# SCH_FILTER_SOL_01_2025-06-17.net
KiCad netlist of a schematic drawn in EasyEDA
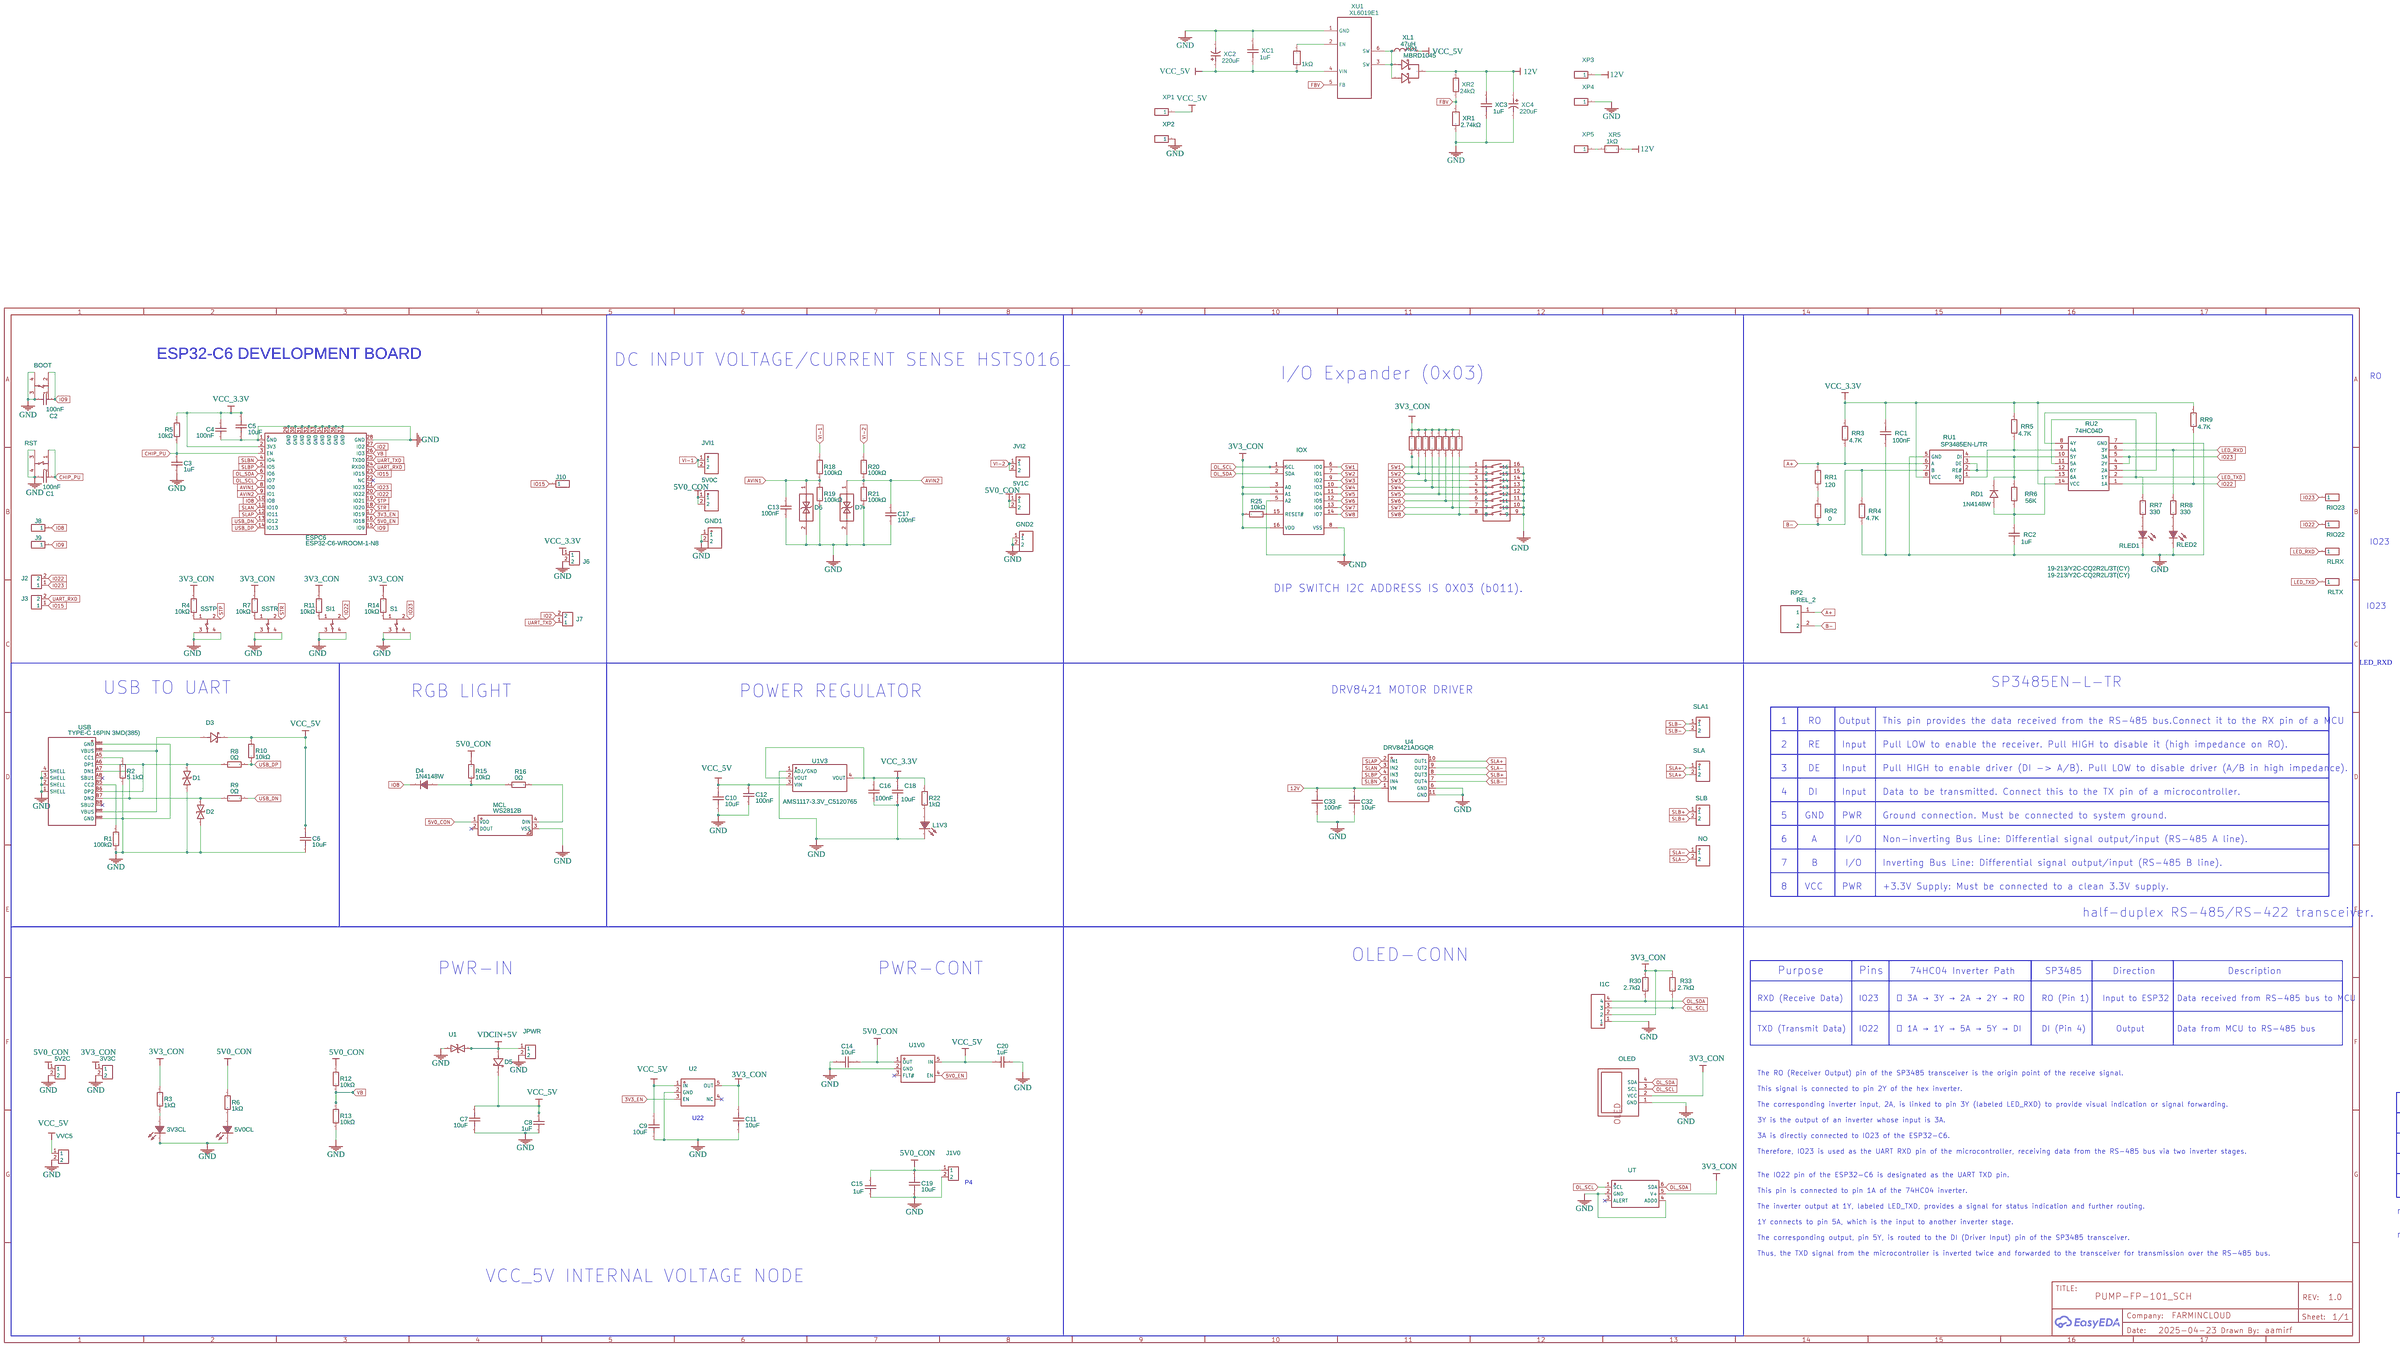
[diagram p0: schematic sheet]

(export (version "E")
  (design (tool "Eeschema 10.0.6"))
  (components
    (comp (ref "3V3C") (value "HD_1X2_2.54") (libsource (lib "") (part "HD_1X2_2.54_2")))
    (comp (ref "3V3CL")
      (value "KT-0603R")
      (fields (field (name "Manufacturer") "KENTO"))
      (libsource (lib "") (part "KT-0603R"))
    )
    (comp (ref "5V0C")
      (value "2060-451/998-404")
      (fields (field (name "Manufacturer") "WAGO(万可)"))
      (libsource (lib "") (part "2060-451/998-404_6"))
    )
    (comp (ref "5V0CL")
      (value "KT-0603R")
      (fields (field (name "Manufacturer") "KENTO"))
      (libsource (lib "") (part "KT-0603R_1"))
    )
    (comp (ref "5V1C")
      (value "2060-471/998-404")
      (fields (field (name "Manufacturer Part") "2060-451/998-404") (field (name "Manufacturer") "WAGO(万可)"))
      (libsource (lib "") (part "2060-451/998-404_4"))
    )
    (comp (ref "5V2C") (value "HD_1X2_2.54") (libsource (lib "") (part "HD_1X2_2.54_3")))
    (comp (ref "BOOT")
      (value "TS-1102SD-A-Q-R")
      (fields (field (name "Manufacturer") "XKB Connectivity(中国星坤)"))
      (libsource (lib "") (part "TS-1102SD-A-Q-R_3"))
    )
    (comp (ref "C1")
      (value "100nF")
      (fields
        (field (name "Manufacturer Part") "CL21B104KCFNNNE")
        (field (name "Manufacturer") "SAMSUNG(三星)")
      )
      (libsource (lib "") (part "CL21B104KCFNNNE_3"))
    )
    (comp (ref "C2")
      (value "100nF")
      (fields
        (field (name "Manufacturer Part") "CL21B104KCFNNNE")
        (field (name "Manufacturer") "SAMSUNG(三星)")
      )
      (libsource (lib "") (part "CL21B104KCFNNNE_2"))
    )
    (comp (ref "C3")
      (value "1uF")
      (fields
        (field (name "Manufacturer Part") "CL21B105KBFNNNE")
        (field (name "Manufacturer") "SAMSUNG(三星)")
      )
      (libsource (lib "") (part "CL21B105KBFNNNE_2"))
    )
    (comp (ref "C4")
      (value "100nF")
      (fields
        (field (name "Manufacturer Part") "CL21B104KCFNNNE")
        (field (name "Manufacturer") "SAMSUNG(三星)")
      )
      (libsource (lib "") (part "CL21B104KCFNNNE"))
    )
    (comp (ref "C5")
      (value "10uF")
      (fields
        (field (name "Manufacturer Part") "CL21A106KAYNNNE")
        (field (name "Manufacturer") "SAMSUNG(三星)")
      )
      (libsource (lib "") (part "CL21A106KAYNNNE"))
    )
    (comp (ref "C6")
      (value "10uF")
      (fields
        (field (name "Manufacturer Part") "CL21A106KAYNNNE")
        (field (name "Manufacturer") "SAMSUNG(三星)")
      )
      (libsource (lib "") (part "CL21A106KAYNNNE"))
    )
    (comp (ref "C7")
      (value "10uF")
      (fields
        (field (name "Manufacturer Part") "CL21A106KAYNNNE")
        (field (name "Manufacturer") "SAMSUNG(三星)")
      )
      (libsource (lib "") (part "CL21A106KAYNNNE_2"))
    )
    (comp (ref "C8")
      (value "1uF")
      (fields
        (field (name "Manufacturer Part") "CL21B105KBFNNNE")
        (field (name "Manufacturer") "SAMSUNG(三星)")
      )
      (libsource (lib "") (part "CL21B105KBFNNNE"))
    )
    (comp (ref "C9")
      (value "10uF")
      (fields
        (field (name "Manufacturer Part") "CL21A106KAYNNNE")
        (field (name "Manufacturer") "SAMSUNG(三星)")
      )
      (libsource (lib "") (part "CL21A106KAYNNNE_2"))
    )
    (comp (ref "C10")
      (value "10uF")
      (fields
        (field (name "Manufacturer Part") "CL21A106KAYNNNE")
        (field (name "Manufacturer") "SAMSUNG(三星)")
      )
      (libsource (lib "") (part "CL21A106KAYNNNE"))
    )
    (comp (ref "C11")
      (value "10uF")
      (fields
        (field (name "Manufacturer Part") "CL21A106KAYNNNE")
        (field (name "Manufacturer") "SAMSUNG(三星)")
      )
      (libsource (lib "") (part "CL21A106KAYNNNE"))
    )
    (comp (ref "C12")
      (value "100nF")
      (fields
        (field (name "Manufacturer Part") "CL21B104KCFNNNE")
        (field (name "Manufacturer") "SAMSUNG(三星)")
      )
      (libsource (lib "") (part "CL21B104KCFNNNE_1"))
    )
    (comp (ref "C13")
      (value "100nF")
      (fields
        (field (name "Manufacturer Part") "CL21B104KCFNNNE")
        (field (name "Manufacturer") "SAMSUNG(三星)")
      )
      (libsource (lib "") (part "CL21B104KCFNNNE"))
    )
    (comp (ref "C14")
      (value "10uF")
      (fields
        (field (name "Manufacturer Part") "CL21A106KAYNNNE")
        (field (name "Manufacturer") "SAMSUNG(三星)")
      )
      (libsource (lib "") (part "CL21A106KAYNNNE_1"))
    )
    (comp (ref "C15")
      (value "1uF")
      (fields
        (field (name "Manufacturer Part") "CL21B105KBFNNNE")
        (field (name "Manufacturer") "SAMSUNG(三星)")
      )
      (libsource (lib "") (part "CL21B105KBFNNNE"))
    )
    (comp (ref "C16")
      (value "100nF")
      (fields
        (field (name "Manufacturer Part") "CL21B104KCFNNNE")
        (field (name "Manufacturer") "SAMSUNG(三星)")
      )
      (libsource (lib "") (part "CL21B104KCFNNNE"))
    )
    (comp (ref "C17")
      (value "100nF")
      (fields
        (field (name "Manufacturer Part") "CL21B104KCFNNNE")
        (field (name "Manufacturer") "SAMSUNG(三星)")
      )
      (libsource (lib "") (part "CL21B104KCFNNNE_1"))
    )
    (comp (ref "C18")
      (value "10uF")
      (fields
        (field (name "Manufacturer Part") "CL21A106KAYNNNE")
        (field (name "Manufacturer") "SAMSUNG(三星)")
      )
      (libsource (lib "") (part "CL21A106KAYNNNE"))
    )
    (comp (ref "C19")
      (value "10uF")
      (fields
        (field (name "Manufacturer Part") "CL21A106KAYNNNE")
        (field (name "Manufacturer") "SAMSUNG(三星)")
      )
      (libsource (lib "") (part "CL21A106KAYNNNE"))
    )
    (comp (ref "C20")
      (value "1uF")
      (fields
        (field (name "Manufacturer Part") "CL21B105KBFNNNE")
        (field (name "Manufacturer") "SAMSUNG(三星)")
      )
      (libsource (lib "") (part "CL21B105KBFNNNE_1"))
    )
    (comp (ref "C32")
      (value "10uF")
      (fields (field (name "Manufacturer Part") "CGA4J1X7R0J106M125AD") (field (name "Manufacturer") "TDK"))
      (libsource (lib "") (part "CGA4J1X7R0J106M125AD"))
    )
    (comp (ref "C33")
      (value "100nF")
      (fields (field (name "Manufacturer Part") "CGA4J3X7T2E104K125AA") (field (name "Manufacturer") "TDK"))
      (libsource (lib "") (part "CGA4J3X7T2E104K125AA_C5331016"))
    )
    (comp (ref "D1")
      (value "LESD5D5.0CT1G")
      (fields (field (name "Manufacturer") "LRC(乐山无线电)"))
      (libsource (lib "") (part "LESD5D5.0CT1G"))
    )
    (comp (ref "D2")
      (value "LESD5D5.0CT1G")
      (fields (field (name "Manufacturer") "LRC(乐山无线电)"))
      (libsource (lib "") (part "LESD5D5.0CT1G"))
    )
    (comp (ref "D3")
      (value "K1N5819HW-7-F")
      (fields (field (name "Manufacturer") "KUU"))
      (libsource (lib "") (part "K1N5819HW-7-F"))
    )
    (comp (ref "D4")
      (value "1N4148W")
      (fields (field (name "Manufacturer") "HT(金誉)"))
      (libsource (lib "") (part "1N4148W"))
    )
    (comp (ref "D5")
      (value "K1N5819HW-7-F")
      (fields (field (name "Manufacturer") "KUU"))
      (libsource (lib "") (part "K1N5819HW-7-F_1"))
    )
    (comp (ref "D6")
      (value "KESD5311X")
      (fields (field (name "Manufacturer") "KUU"))
      (libsource (lib "") (part "KESD5311X"))
    )
    (comp (ref "D7")
      (value "KESD5311X")
      (fields (field (name "Manufacturer") "KUU"))
      (libsource (lib "") (part "KESD5311X"))
    )
    (comp (ref "ESPC6")
      (value "ESP32-C6-WROOM-1-N8")
      (fields (field (name "Manufacturer") "ESPRESSIF(乐鑫)"))
      (libsource (lib "") (part "ESP32-C6-WROOM-1-N8"))
    )
    (comp (ref "GND1")
      (value "2060-451/998-404")
      (fields (field (name "Manufacturer") "WAGO(万可)"))
      (libsource (lib "") (part "2060-451/998-404_2"))
    )
    (comp (ref "GND2")
      (value "2060-451/998-404")
      (fields (field (name "Manufacturer") "WAGO(万可)"))
      (libsource (lib "") (part "2060-451/998-404_2"))
    )
    (comp (ref "I1C")
      (value "X6511WV-04H-C30D60")
      (fields (field (name "Manufacturer") "XKB Connectivity(中国星坤)"))
      (libsource (lib "") (part "X6511WV-04H-C30D60"))
    )
    (comp (ref "IOS")
      (value "THS108J")
      (fields (field (name "Manufacturer") "ROCPU Switches(台普)"))
      (libsource (lib "") (part "THS108J"))
    )
    (comp (ref "IOX")
      (value "PCA9557PW,118")
      (fields (field (name "Manufacturer") "NXP(恩智浦)"))
      (libsource (lib "") (part "PCA9557PW,118"))
    )
    (comp (ref "J1V0") (value "HD_1X2_2.54") (libsource (lib "") (part "HD_1X2_2.54_6")))
    (comp (ref "J2") (value "HD_1X2_2.54") (libsource (lib "") (part "HD_1X2_2.54_5")))
    (comp (ref "J3") (value "HD_1X2_2.54") (libsource (lib "") (part "HD_1X2_2.54_5")))
    (comp (ref "J6") (value "HD_1X2_2.54") (libsource (lib "") (part "HD_1X2_2.54_4")))
    (comp (ref "J7") (value "HD_1X2_2.54") (libsource (lib "") (part "HD_1X2_2.54")))
    (comp (ref "J8") (value "HDR-M-2.54_1x1") (libsource (lib "") (part "HDR-M-2.54_1x1")))
    (comp (ref "J9") (value "HDR-M-2.54_1x1") (libsource (lib "") (part "HDR-M-2.54_1x1")))
    (comp (ref "J10") (value "HDR-M-2.54_1x1") (libsource (lib "") (part "HDR-M-2.54_1x1_1")))
    (comp (ref "JPWR") (value "HD_1X2_2.54") (libsource (lib "") (part "HD_1X2_2.54_1")))
    (comp (ref "JVI1")
      (value "2060-451/998-404")
      (fields (field (name "Manufacturer") "WAGO(万可)"))
      (libsource (lib "") (part "2060-451/998-404"))
    )
    (comp (ref "JVI2")
      (value "2060-451/998-404")
      (fields (field (name "Manufacturer") "WAGO(万可)"))
      (libsource (lib "") (part "2060-451/998-404"))
    )
    (comp (ref "L1V3")
      (value "KT-0603R")
      (fields (field (name "Manufacturer") "KENTO"))
      (libsource (lib "") (part "KT-0603R_2"))
    )
    (comp (ref "MCL")
      (value "WS2812B")
      (fields (field (name "Manufacturer Part") "WS2812B-V3") (field (name "Manufacturer") "worldsemi"))
      (libsource (lib "") (part "WS2812B"))
    )
    (comp (ref "NO")
      (value "2060-451/998-404")
      (fields (field (name "Manufacturer") "WAGO(万可)"))
      (libsource (lib "") (part "2060-451/998-404_5"))
    )
    (comp (ref "OLED")
      (value "GRINNAN_OLED 128X64 0,96\" I2C 4PIN")
      (fields (field (name "Manufacturer Part") "SSD1306 I2C OLED"))
      (libsource (lib "") (part "GRINNAN_OLED 128X64 0,96{dblquote} I2C 4PIN"))
    )
    (comp (ref "R1")
      (value "100kΩ")
      (fields
        (field (name "Manufacturer Part") "0805W8F1003T5E")
        (field (name "Manufacturer") "UNI-ROYAL(厚声)")
      )
      (libsource (lib "") (part "0805W8F1003T5E_C149504"))
    )
    (comp (ref "R2")
      (value "5.1kΩ")
      (fields
        (field (name "Manufacturer Part") "0805W8F5101T5E")
        (field (name "Manufacturer") "UNI-ROYAL(厚声)")
      )
      (libsource (lib "") (part "0805W8F5101T5E"))
    )
    (comp (ref "R3")
      (value "1kΩ")
      (fields
        (field (name "Manufacturer Part") "0805W8F1001T5E")
        (field (name "Manufacturer") "UNI-ROYAL(厚声)")
      )
      (libsource (lib "") (part "0805W8F1001T5E"))
    )
    (comp (ref "R4")
      (value "10kΩ")
      (fields
        (field (name "Manufacturer Part") "0805W8F1002T5E")
        (field (name "Manufacturer") "UNI-ROYAL(厚声)")
      )
      (libsource (lib "") (part "0805W8F1002T5E_1"))
    )
    (comp (ref "R5")
      (value "10kΩ")
      (fields
        (field (name "Manufacturer Part") "0805W8F1002T5E")
        (field (name "Manufacturer") "UNI-ROYAL(厚声)")
      )
      (libsource (lib "") (part "0805W8F1002T5E_1"))
    )
    (comp (ref "R6")
      (value "1kΩ")
      (fields
        (field (name "Manufacturer Part") "0805W8F1001T5E")
        (field (name "Manufacturer") "UNI-ROYAL(厚声)")
      )
      (libsource (lib "") (part "0805W8F1001T5E"))
    )
    (comp (ref "R7")
      (value "10kΩ")
      (fields
        (field (name "Manufacturer Part") "0805W8F1002T5E")
        (field (name "Manufacturer") "UNI-ROYAL(厚声)")
      )
      (libsource (lib "") (part "0805W8F1002T5E_1"))
    )
    (comp (ref "R8")
      (value "0Ω")
      (fields
        (field (name "Manufacturer Part") "0805W8F0000T5E")
        (field (name "Manufacturer") "UNI-ROYAL(厚声)")
      )
      (libsource (lib "") (part "0805W8F0000T5E"))
    )
    (comp (ref "R9")
      (value "0Ω")
      (fields
        (field (name "Manufacturer Part") "0805W8F0000T5E")
        (field (name "Manufacturer") "UNI-ROYAL(厚声)")
      )
      (libsource (lib "") (part "0805W8F0000T5E"))
    )
    (comp (ref "R10")
      (value "10kΩ")
      (fields
        (field (name "Manufacturer Part") "0805W8F1002T5E")
        (field (name "Manufacturer") "UNI-ROYAL(厚声)")
      )
      (libsource (lib "") (part "0805W8F1002T5E_1"))
    )
    (comp (ref "R11")
      (value "10kΩ")
      (fields
        (field (name "Manufacturer Part") "0805W8F1002T5E")
        (field (name "Manufacturer") "UNI-ROYAL(厚声)")
      )
      (libsource (lib "") (part "0805W8F1002T5E_1"))
    )
    (comp (ref "R12")
      (value "10kΩ")
      (fields
        (field (name "Manufacturer Part") "0805W8F1002T5E")
        (field (name "Manufacturer") "UNI-ROYAL(厚声)")
      )
      (libsource (lib "") (part "0805W8F1002T5E_1"))
    )
    (comp (ref "R13")
      (value "10kΩ")
      (fields
        (field (name "Manufacturer Part") "0805W8F1002T5E")
        (field (name "Manufacturer") "UNI-ROYAL(厚声)")
      )
      (libsource (lib "") (part "0805W8F1002T5E_1"))
    )
    (comp (ref "R14")
      (value "10kΩ")
      (fields
        (field (name "Manufacturer Part") "0805W8F1002T5E")
        (field (name "Manufacturer") "UNI-ROYAL(厚声)")
      )
      (libsource (lib "") (part "0805W8F1002T5E_1"))
    )
    (comp (ref "R15")
      (value "10kΩ")
      (fields
        (field (name "Manufacturer Part") "0805W8F1002T5E")
        (field (name "Manufacturer") "UNI-ROYAL(厚声)")
      )
      (libsource (lib "") (part "0805W8F1002T5E_1"))
    )
    (comp (ref "R16")
      (value "0Ω")
      (fields
        (field (name "Manufacturer Part") "0805W8F0000T5E")
        (field (name "Manufacturer") "UNI-ROYAL(厚声)")
      )
      (libsource (lib "") (part "0805W8F0000T5E"))
    )
    (comp (ref "R18")
      (value "100kΩ")
      (fields
        (field (name "Manufacturer Part") "0805W8F1003T5E")
        (field (name "Manufacturer") "UNI-ROYAL(厚声)")
      )
      (libsource (lib "") (part "0805W8F1003T5E_C149504"))
    )
    (comp (ref "R19")
      (value "100kΩ")
      (fields
        (field (name "Manufacturer Part") "0805W8F1003T5E")
        (field (name "Manufacturer") "UNI-ROYAL(厚声)")
      )
      (libsource (lib "") (part "0805W8F1003T5E_C149504"))
    )
    (comp (ref "R20")
      (value "100kΩ")
      (fields
        (field (name "Manufacturer Part") "0805W8F1003T5E")
        (field (name "Manufacturer") "UNI-ROYAL(厚声)")
      )
      (libsource (lib "") (part "0805W8F1003T5E_C149504"))
    )
    (comp (ref "R21")
      (value "100kΩ")
      (fields
        (field (name "Manufacturer Part") "0805W8F1003T5E")
        (field (name "Manufacturer") "UNI-ROYAL(厚声)")
      )
      (libsource (lib "") (part "0805W8F1003T5E_C149504"))
    )
    (comp (ref "R22")
      (value "1kΩ")
      (fields
        (field (name "Manufacturer Part") "0805W8F1001T5E")
        (field (name "Manufacturer") "UNI-ROYAL(厚声)")
      )
      (libsource (lib "") (part "0805W8F1001T5E"))
    )
    (comp (ref "R25")
      (value "10kΩ")
      (fields
        (field (name "Manufacturer Part") "0805W8F1002T5E")
        (field (name "Manufacturer") "UNI-ROYAL(厚声)")
      )
      (libsource (lib "") (part "0805W8F1002T5E"))
    )
    (comp (ref "R30")
      (value "2.7kΩ")
      (fields
        (field (name "Manufacturer Part") "0805W8F2701T5E")
        (field (name "Manufacturer") "UNI-ROYAL(厚声)")
      )
      (libsource (lib "") (part "0805W8F2701T5E"))
    )
    (comp (ref "R33")
      (value "2.7kΩ")
      (fields
        (field (name "Manufacturer Part") "0805W8F2701T5E")
        (field (name "Manufacturer") "UNI-ROYAL(厚声)")
      )
      (libsource (lib "") (part "0805W8F2701T5E"))
    )
    (comp (ref "RC1")
      (value "100nF")
      (fields (field (name "Manufacturer Part") "CC0603KRX7R9BB104") (field (name "Manufacturer") "YAGEO"))
      (libsource (lib "") (part "CC0603KRX7R9BB104"))
    )
    (comp (ref "RC2")
      (value "1uF")
      (fields (field (name "Manufacturer Part") "CL10A105KB8NNNC") (field (name "Manufacturer") "SAMSUNG"))
      (libsource (lib "") (part "CL10A105KB8NNNC"))
    )
    (comp (ref "RD1")
      (value "1N4148W")
      (fields (field (name "Manufacturer") "SEMTECH"))
      (libsource (lib "") (part "1N4148W_C81598"))
    )
    (comp (ref "RIO22")
      (value "Header-Male-2.54_1x1")
      (fields (field (name "Manufacturer Part") "2.54-1*1P针") (field (name "Manufacturer") "BOOMELE(博穆精密)"))
      (libsource (lib "") (part "Header-Male-2.54_1x1_1"))
    )
    (comp (ref "RIO23")
      (value "Header-Male-2.54_1x1")
      (fields (field (name "Manufacturer Part") "2.54-1*1P针") (field (name "Manufacturer") "BOOMELE(博穆精密)"))
      (libsource (lib "") (part "Header-Male-2.54_1x1_1"))
    )
    (comp (ref "RLED1")
      (value "19-213/Y2C-CQ2R2L/3T(CY)")
      (fields (field (name "Manufacturer") "EVERLIGHT"))
      (libsource (lib "") (part "19-213/Y2C-CQ2R2L/3T(CY)"))
    )
    (comp (ref "RLED2")
      (value "19-213/Y2C-CQ2R2L/3T(CY)")
      (fields (field (name "Manufacturer") "EVERLIGHT"))
      (libsource (lib "") (part "19-213/Y2C-CQ2R2L/3T(CY)"))
    )
    (comp (ref "RLRX")
      (value "Header-Male-2.54_1x1")
      (fields (field (name "Manufacturer Part") "2.54-1*1P针") (field (name "Manufacturer") "BOOMELE(博穆精密)"))
      (libsource (lib "") (part "Header-Male-2.54_1x1_2"))
    )
    (comp (ref "RLTX")
      (value "Header-Male-2.54_1x1")
      (fields (field (name "Manufacturer Part") "2.54-1*1P针") (field (name "Manufacturer") "BOOMELE(博穆精密)"))
      (libsource (lib "") (part "Header-Male-2.54_1x1_3"))
    )
    (comp (ref "RP2")
      (value "REL_2")
      (fields
        (field (name "Manufacturer Part") "WJ300V-5.0-2P")
        (field (name "Manufacturer") "KANGNEX(康奈克斯电气)")
      )
      (libsource (lib "") (part "WJ300V-5.0-2P"))
    )
    (comp (ref "RR1")
      (value "120")
      (fields (field (name "Manufacturer Part") "0603WAF1200T5E") (field (name "Manufacturer") "UniOhm"))
      (libsource (lib "") (part "0603WAF1200T5E"))
    )
    (comp (ref "RR2")
      (value "0")
      (fields (field (name "Manufacturer Part") "0603WAF0000T5E") (field (name "Manufacturer") "UniOhm"))
      (libsource (lib "") (part "0603WAF0000T5E"))
    )
    (comp (ref "RR3")
      (value "4.7K")
      (fields (field (name "Manufacturer Part") "0603WAF4701T5E") (field (name "Manufacturer") "UniOhm"))
      (libsource (lib "") (part "0603WAF4701T5E"))
    )
    (comp (ref "RR4")
      (value "4.7K")
      (fields (field (name "Manufacturer Part") "0603WAF4701T5E") (field (name "Manufacturer") "UniOhm"))
      (libsource (lib "") (part "0603WAF4701T5E"))
    )
    (comp (ref "RR5")
      (value "4.7K")
      (fields (field (name "Manufacturer Part") "0603WAF4701T5E") (field (name "Manufacturer") "UniOhm"))
      (libsource (lib "") (part "0603WAF4701T5E"))
    )
    (comp (ref "RR6")
      (value "56K")
      (fields (field (name "Manufacturer Part") "0603WAF5602T5E") (field (name "Manufacturer") "UniOhm"))
      (libsource (lib "") (part "0603WAF5602T5E"))
    )
    (comp (ref "RR7")
      (value "330")
      (fields (field (name "Manufacturer Part") "0603WAF3300T5E") (field (name "Manufacturer") "UniOhm"))
      (libsource (lib "") (part "0603WAF3300T5E"))
    )
    (comp (ref "RR8")
      (value "330")
      (fields (field (name "Manufacturer Part") "0603WAF3300T5E") (field (name "Manufacturer") "UniOhm"))
      (libsource (lib "") (part "0603WAF3300T5E_1"))
    )
    (comp (ref "RR9")
      (value "4.7K")
      (fields (field (name "Manufacturer Part") "0603WAF4701T5E") (field (name "Manufacturer") "UniOhm"))
      (libsource (lib "") (part "0603WAF4701T5E"))
    )
    (comp (ref "RST")
      (value "TS-1102SD-A-Q-R")
      (fields (field (name "Manufacturer") "XKB Connectivity(中国星坤)"))
      (libsource (lib "") (part "TS-1102SD-A-Q-R_1"))
    )
    (comp (ref "RU1")
      (value "SP3485EN-L/TR")
      (fields (field (name "Manufacturer") "EXAR"))
      (libsource (lib "") (part "SP3485EN-L/TR"))
    )
    (comp (ref "RU2")
      (value "74HC04D")
      (fields (field (name "Manufacturer Part") "74HC04D,653") (field (name "Manufacturer") "Nexperia"))
      (libsource (lib "") (part "Unknown_3190_-2390"))
    )
    (comp (ref "S1")
      (value "TS-1102SD-A-Q-R")
      (fields (field (name "Manufacturer") "XKB Connectivity(中国星坤)"))
      (libsource (lib "") (part "TS-1102SD-A-Q-R_5"))
    )
    (comp (ref "S2")
      (value "10kΩ")
      (fields
        (field (name "Manufacturer Part") "0402WGF1002TCE")
        (field (name "Manufacturer") "UNI-ROYAL(厚声)")
      )
      (libsource (lib "") (part "0402WGF1002TCE"))
    )
    (comp (ref "S3")
      (value "10kΩ")
      (fields
        (field (name "Manufacturer Part") "0402WGF1002TCE")
        (field (name "Manufacturer") "UNI-ROYAL(厚声)")
      )
      (libsource (lib "") (part "0402WGF1002TCE"))
    )
    (comp (ref "S4")
      (value "10kΩ")
      (fields
        (field (name "Manufacturer Part") "0402WGF1002TCE")
        (field (name "Manufacturer") "UNI-ROYAL(厚声)")
      )
      (libsource (lib "") (part "0402WGF1002TCE"))
    )
    (comp (ref "S5")
      (value "10kΩ")
      (fields
        (field (name "Manufacturer Part") "0402WGF1002TCE")
        (field (name "Manufacturer") "UNI-ROYAL(厚声)")
      )
      (libsource (lib "") (part "0402WGF1002TCE"))
    )
    (comp (ref "S6")
      (value "10kΩ")
      (fields
        (field (name "Manufacturer Part") "0402WGF1002TCE")
        (field (name "Manufacturer") "UNI-ROYAL(厚声)")
      )
      (libsource (lib "") (part "0402WGF1002TCE"))
    )
    (comp (ref "S7")
      (value "10kΩ")
      (fields
        (field (name "Manufacturer Part") "0402WGF1002TCE")
        (field (name "Manufacturer") "UNI-ROYAL(厚声)")
      )
      (libsource (lib "") (part "0402WGF1002TCE"))
    )
    (comp (ref "S8")
      (value "10kΩ")
      (fields
        (field (name "Manufacturer Part") "0402WGF1002TCE")
        (field (name "Manufacturer") "UNI-ROYAL(厚声)")
      )
      (libsource (lib "") (part "0402WGF1002TCE"))
    )
    (comp (ref "S9")
      (value "10kΩ")
      (fields
        (field (name "Manufacturer Part") "0402WGF1002TCE")
        (field (name "Manufacturer") "UNI-ROYAL(厚声)")
      )
      (libsource (lib "") (part "0402WGF1002TCE"))
    )
    (comp (ref "SI1")
      (value "TS-1102SD-A-Q-R")
      (fields (field (name "Manufacturer") "XKB Connectivity(中国星坤)"))
      (libsource (lib "") (part "TS-1102SD-A-Q-R"))
    )
    (comp (ref "SLA")
      (value "2060-451/998-404")
      (fields (field (name "Manufacturer") "WAGO(万可)"))
      (libsource (lib "") (part "2060-451/998-404_1"))
    )
    (comp (ref "SLA1")
      (value "2060-451/998-404")
      (fields (field (name "Manufacturer") "WAGO(万可)"))
      (libsource (lib "") (part "2060-451/998-404_1"))
    )
    (comp (ref "SLB")
      (value "2060-451/998-404")
      (fields (field (name "Manufacturer") "WAGO(万可)"))
      (libsource (lib "") (part "2060-451/998-404_3"))
    )
    (comp (ref "SSTP")
      (value "TS-1102SD-A-Q-R")
      (fields (field (name "Manufacturer") "XKB Connectivity(中国星坤)"))
      (libsource (lib "") (part "TS-1102SD-A-Q-R_4"))
    )
    (comp (ref "SSTR")
      (value "TS-1102SD-A-Q-R")
      (fields (field (name "Manufacturer") "XKB Connectivity(中国星坤)"))
      (libsource (lib "") (part "TS-1102SD-A-Q-R_2"))
    )
    (comp (ref "U1")
      (value "LESD5D5.0CT1G_C5246195")
      (fields
        (field (name "Manufacturer Part") "LESD5D5.0CT1G")
        (field (name "Manufacturer") "Leiditech(雷卯电子)")
      )
      (libsource (lib "") (part "LESD5D5.0CT1G_C5246195"))
    )
    (comp (ref "U1V0")
      (value "TPS2065DDBVR")
      (fields (field (name "Manufacturer") "TI(德州仪器)"))
      (libsource (lib "") (part "TPS2065DDBVR"))
    )
    (comp (ref "U1V3")
      (value "AMS1117-3.3V_C5120765")
      (fields (field (name "Manufacturer Part") "AMS1117-3.3V") (field (name "Manufacturer") "MSKSEMI(美森科)"))
      (libsource (lib "") (part "AMS1117-3.3V_C5120765"))
    )
    (comp (ref "U2")
      (value "TLV75533PDBVR")
      (fields (field (name "Manufacturer") "TI(德州仪器)"))
      (libsource (lib "") (part "TLV75533PDBVR"))
    )
    (comp (ref "U4")
      (value "DRV8421ADGQR")
      (fields (field (name "Manufacturer") "TI(德州仪器)"))
      (libsource (lib "") (part "DRV8421ADGQR"))
    )
    (comp (ref "USB")
      (value "TYPE-C 16PIN 3MD(385)")
      (fields (field (name "Manufacturer") "SHOU HAN(首韩)"))
      (libsource (lib "") (part "TYPE-C 16PIN 3MD(385)"))
    )
    (comp (ref "UT")
      (value "TMP112BIDRLR_C3019123")
      (fields (field (name "Manufacturer Part") "TMP112BIDRLR") (field (name "Manufacturer") "UMW(友台半导体)"))
      (libsource (lib "") (part "TMP112BIDRLR_C3019123"))
    )
    (comp (ref "VVC5") (value "HD_1X2_2.54") (libsource (lib "") (part "HD_1X2_2.54_7")))
    (comp (ref "XC1")
      (value "1uF")
      (fields (field (name "Manufacturer Part") "0805B105M500NT") (field (name "Manufacturer") "FH(风华)"))
      (libsource (lib "") (part "0805B105M500NT"))
    )
    (comp (ref "XC2")
      (value "220uF")
      (fields
        (field (name "Manufacturer Part") "JBLM2221M025C090RTM 220UF 25V")
        (field (name "Manufacturer") "DMBJ(振宝佳)")
      )
      (libsource (lib "") (part "JBLM2221M025C090RTM 220UF 25V"))
    )
    (comp (ref "XC3")
      (value "1uF")
      (fields (field (name "Manufacturer Part") "0805B105M500NT") (field (name "Manufacturer") "FH(风华)"))
      (libsource (lib "") (part "0805B105M500NT"))
    )
    (comp (ref "XC4")
      (value "220uF")
      (fields
        (field (name "Manufacturer Part") "JBLM2221M025C090RTM 220UF 25V")
        (field (name "Manufacturer") "DMBJ(振宝佳)")
      )
      (libsource (lib "") (part "JBLM2221M025C090RTM 220UF 25V_1"))
    )
    (comp (ref "XD1")
      (value "MBRD1045")
      (fields (field (name "Manufacturer") "GOODWORK(固得沃克)"))
      (libsource (lib "") (part "MBRD1045"))
    )
    (comp (ref "XL1")
      (value "47uH")
      (fields (field (name "Manufacturer Part") "SL1050-470M") (field (name "Manufacturer") "台湾陆海"))
      (libsource (lib "") (part "SL1050-470M"))
    )
    (comp (ref "XP1")
      (value "Header-Male-2.54_1x1")
      (fields (field (name "Manufacturer Part") "2.54-1*1P针") (field (name "Manufacturer") "BOOMELE(博穆精密)"))
      (libsource (lib "") (part "Header-Male-2.54_1x1"))
    )
    (comp (ref "XP2")
      (value "Header-Male-2.54_1x1")
      (fields (field (name "Manufacturer Part") "2.54-1*1P针") (field (name "Manufacturer") "BOOMELE(博穆精密)"))
      (libsource (lib "") (part "Header-Male-2.54_1x1"))
    )
    (comp (ref "XP3")
      (value "Header-Male-2.54_1x1")
      (fields (field (name "Manufacturer Part") "2.54-1*1P针") (field (name "Manufacturer") "BOOMELE(博穆精密)"))
      (libsource (lib "") (part "Header-Male-2.54_1x1"))
    )
    (comp (ref "XP4")
      (value "Header-Male-2.54_1x1")
      (fields (field (name "Manufacturer Part") "2.54-1*1P针") (field (name "Manufacturer") "BOOMELE(博穆精密)"))
      (libsource (lib "") (part "Header-Male-2.54_1x1"))
    )
    (comp (ref "XP5")
      (value "Header-Male-2.54_1x1")
      (fields (field (name "Manufacturer Part") "2.54-1*1P针") (field (name "Manufacturer") "BOOMELE(博穆精密)"))
      (libsource (lib "") (part "Header-Male-2.54_1x1"))
    )
    (comp (ref "XR1")
      (value "2.74kΩ")
      (fields (field (name "Manufacturer Part") "PTFR0805B2K74P9") (field (name "Manufacturer") "RESI(开步睿思)"))
      (libsource (lib "") (part "PTFR0805B2K74P9"))
    )
    (comp (ref "XR2")
      (value "24kΩ")
      (fields (field (name "Manufacturer Part") "CR0805-FX-2402ELF") (field (name "Manufacturer") "BOURNS"))
      (libsource (lib "") (part "CR0805-FX-2402ELF"))
    )
    (comp (ref "XR3")
      (value "1kΩ")
      (fields
        (field (name "Manufacturer Part") "SC0805J1001F4ANRH")
        (field (name "Manufacturer") "Sunway(信维通信)")
      )
      (libsource (lib "") (part "SC0805J1001F4ANRH"))
    )
    (comp (ref "XR5")
      (value "1kΩ")
      (fields
        (field (name "Manufacturer Part") "TP0805T1K00P0505Z")
        (field (name "Manufacturer") "EVER OHMS(天二科技)")
      )
      (libsource (lib "") (part "TP0805T1K00P0505Z"))
    )
    (comp (ref "XU1")
      (value "XL6019E1")
      (fields (field (name "Manufacturer") "XLSEMI(芯龙)"))
      (libsource (lib "") (part "XL6019E1"))
    )
  )
  (nets
    (net (code "1") (name "3V3_CON") (class "Default")
      (node (ref "3V3C") (pin "1") (pinfunction "1_1") (pintype "unspecified"))
      (node (ref "C11") (pin "1") (pinfunction "1_1") (pintype "unspecified"))
      (node (ref "I1C") (pin "2") (pinfunction "2_2") (pintype "unspecified"))
      (node (ref "IOX") (pin "16") (pinfunction "VDD_16") (pintype "passive"))
      (node (ref "IOX") (pin "3") (pinfunction "A0_3") (pintype "unspecified"))
      (node (ref "IOX") (pin "4") (pinfunction "A1_4") (pintype "unspecified"))
      (node (ref "OLED") (pin "2") (pinfunction "VCC_2") (pintype "unspecified"))
      (node (ref "R11") (pin "1") (pinfunction "1_1") (pintype "input"))
      (node (ref "R14") (pin "1") (pinfunction "1_1") (pintype "input"))
      (node (ref "R25") (pin "2") (pinfunction "2_2") (pintype "input"))
      (node (ref "R3") (pin "1") (pinfunction "1_1") (pintype "input"))
      (node (ref "R30") (pin "1") (pinfunction "1_1") (pintype "input"))
      (node (ref "R33") (pin "1") (pinfunction "1_1") (pintype "input"))
      (node (ref "R4") (pin "1") (pinfunction "1_1") (pintype "input"))
      (node (ref "R7") (pin "1") (pinfunction "1_1") (pintype "input"))
      (node (ref "S2") (pin "2") (pinfunction "2_2") (pintype "input"))
      (node (ref "S3") (pin "2") (pinfunction "2_2") (pintype "input"))
      (node (ref "S4") (pin "2") (pinfunction "2_2") (pintype "input"))
      (node (ref "S5") (pin "2") (pinfunction "2_2") (pintype "input"))
      (node (ref "S6") (pin "2") (pinfunction "2_2") (pintype "input"))
      (node (ref "S7") (pin "2") (pinfunction "2_2") (pintype "input"))
      (node (ref "S8") (pin "2") (pinfunction "2_2") (pintype "input"))
      (node (ref "S9") (pin "2") (pinfunction "2_2") (pintype "input"))
      (node (ref "U2") (pin "5") (pinfunction "OUT_5") (pintype "unspecified"))
      (node (ref "UT") (pin "5") (pinfunction "V+_5") (pintype "unspecified"))
    )
    (net (code "2") (name "3V3_EN") (class "Default")
      (node (ref "ESPC6") (pin "17") (pinfunction "IO19_17") (pintype "unspecified"))
      (node (ref "U2") (pin "3") (pinfunction "EN_3") (pintype "unspecified"))
    )
    (net (code "3") (name "5V0_CON") (class "Default")
      (node (ref "5V0C") (pin "1") (pinfunction "1_1") (pintype "unspecified"))
      (node (ref "5V0C") (pin "2") (pinfunction "2_2") (pintype "unspecified"))
      (node (ref "5V1C") (pin "1") (pinfunction "1_1") (pintype "unspecified"))
      (node (ref "5V1C") (pin "2") (pinfunction "2_2") (pintype "unspecified"))
      (node (ref "5V2C") (pin "1") (pinfunction "1_1") (pintype "unspecified"))
      (node (ref "C14") (pin "2") (pinfunction "2_2") (pintype "unspecified"))
      (node (ref "C15") (pin "1") (pinfunction "1_1") (pintype "input"))
      (node (ref "C19") (pin "1") (pinfunction "1_1") (pintype "unspecified"))
      (node (ref "J1V0") (pin "1") (pinfunction "1_1") (pintype "unspecified"))
      (node (ref "MCL") (pin "1") (pinfunction "VDD_1") (pintype "unspecified"))
      (node (ref "R12") (pin "1") (pinfunction "1_1") (pintype "input"))
      (node (ref "R15") (pin "1") (pinfunction "1_1") (pintype "input"))
      (node (ref "R6") (pin "1") (pinfunction "1_1") (pintype "input"))
      (node (ref "U1V0") (pin "1") (pinfunction "OUT_1") (pintype "unspecified"))
    )
    (net (code "4") (name "5V0_EN") (class "Default")
      (node (ref "ESPC6") (pin "16") (pinfunction "IO18_16") (pintype "unspecified"))
      (node (ref "U1V0") (pin "4") (pinfunction "EN_4") (pintype "unspecified"))
    )
    (net (code "5") (name "12V") (class "Default")
      (node (ref "C32") (pin "2") (pinfunction "2_2") (pintype "unspecified"))
      (node (ref "C33") (pin "2") (pinfunction "2_2") (pintype "unspecified"))
      (node (ref "U4") (pin "1") (pinfunction "VM_1") (pintype "unspecified"))
      (node (ref "XC3") (pin "2") (pinfunction "2_2") (pintype "unspecified"))
      (node (ref "XC4") (pin "1") (pinfunction "1_1") (pintype "input"))
      (node (ref "XD1") (pin "2") (pinfunction "K_2") (pintype "unspecified"))
      (node (ref "XP3") (pin "1") (pinfunction "1_1") (pintype "input"))
      (node (ref "XR2") (pin "2") (pinfunction "2_2") (pintype "unspecified"))
      (node (ref "XR5") (pin "2") (pinfunction "2_2") (pintype "unspecified"))
    )
    (net (code "6") (name "A+") (class "Default")
      (node (ref "RP2") (pin "1") (pinfunction "1_1") (pintype "unspecified"))
      (node (ref "RR1") (pin "1") (pinfunction "1_1") (pintype "input"))
      (node (ref "RR3") (pin "1") (pinfunction "1_1") (pintype "input"))
      (node (ref "RU1") (pin "6") (pinfunction "A_6") (pintype "unspecified"))
    )
    (net (code "7") (name "AVIN1") (class "Default")
      (node (ref "C13") (pin "1") (pinfunction "1_1") (pintype "input"))
      (node (ref "D6") (pin "1") (pinfunction "1_1") (pintype "unspecified"))
      (node (ref "ESPC6") (pin "8") (pinfunction "IO0_8") (pintype "unspecified"))
      (node (ref "R18") (pin "2") (pinfunction "2_2") (pintype "unspecified"))
      (node (ref "R19") (pin "1") (pinfunction "1_1") (pintype "unspecified"))
    )
    (net (code "8") (name "AVIN2") (class "Default")
      (node (ref "C17") (pin "1") (pinfunction "1_1") (pintype "input"))
      (node (ref "D7") (pin "1") (pinfunction "1_1") (pintype "unspecified"))
      (node (ref "ESPC6") (pin "9") (pinfunction "IO1_9") (pintype "unspecified"))
      (node (ref "R20") (pin "2") (pinfunction "2_2") (pintype "unspecified"))
      (node (ref "R21") (pin "1") (pinfunction "1_1") (pintype "unspecified"))
    )
    (net (code "9") (name "B-") (class "Default")
      (node (ref "RP2") (pin "2") (pinfunction "2_2") (pintype "unspecified"))
      (node (ref "RR2") (pin "2") (pinfunction "2_2") (pintype "input"))
      (node (ref "RR4") (pin "2") (pinfunction "2_2") (pintype "input"))
      (node (ref "RU1") (pin "7") (pinfunction "B_7") (pintype "unspecified"))
    )
    (net (code "10") (name "CHIP_PU") (class "Default")
      (node (ref "C1") (pin "1") (pinfunction "1_1") (pintype "input"))
      (node (ref "C3") (pin "1") (pinfunction "1_1") (pintype "input"))
      (node (ref "ESPC6") (pin "3") (pinfunction "EN_3") (pintype "unspecified"))
      (node (ref "R5") (pin "2") (pinfunction "2_2") (pintype "input"))
      (node (ref "RST") (pin "1") (pinfunction "1_1") (pintype "unspecified"))
      (node (ref "RST") (pin "2") (pinfunction "2_2") (pintype "unspecified"))
    )
    (net (code "11") (name "FBV") (class "Default")
      (node (ref "XR1") (pin "2") (pinfunction "2_2") (pintype "unspecified"))
      (node (ref "XR2") (pin "1") (pinfunction "1_1") (pintype "unspecified"))
      (node (ref "XU1") (pin "5") (pinfunction "FB_5") (pintype "unspecified"))
    )
    (net (code "12") (name "GND") (class "Default")
      (node (ref "3V3C") (pin "2") (pinfunction "2_2") (pintype "unspecified"))
      (node (ref "3V3CL") (pin "1") (pinfunction "K_1") (pintype "unspecified"))
      (node (ref "5V0CL") (pin "1") (pinfunction "K_1") (pintype "unspecified"))
      (node (ref "5V2C") (pin "2") (pinfunction "2_2") (pintype "unspecified"))
      (node (ref "BOOT") (pin "3") (pinfunction "3_3") (pintype "unspecified"))
      (node (ref "BOOT") (pin "4") (pinfunction "4_4") (pintype "unspecified"))
      (node (ref "C1") (pin "2") (pinfunction "2_2") (pintype "input"))
      (node (ref "C10") (pin "2") (pinfunction "2_2") (pintype "unspecified"))
      (node (ref "C11") (pin "2") (pinfunction "2_2") (pintype "unspecified"))
      (node (ref "C12") (pin "2") (pinfunction "2_2") (pintype "input"))
      (node (ref "C13") (pin "2") (pinfunction "2_2") (pintype "input"))
      (node (ref "C14") (pin "1") (pinfunction "1_1") (pintype "unspecified"))
      (node (ref "C15") (pin "2") (pinfunction "2_2") (pintype "input"))
      (node (ref "C16") (pin "2") (pinfunction "2_2") (pintype "input"))
      (node (ref "C17") (pin "2") (pinfunction "2_2") (pintype "input"))
      (node (ref "C18") (pin "2") (pinfunction "2_2") (pintype "unspecified"))
      (node (ref "C19") (pin "2") (pinfunction "2_2") (pintype "unspecified"))
      (node (ref "C2") (pin "1") (pinfunction "1_1") (pintype "input"))
      (node (ref "C20") (pin "1") (pinfunction "1_1") (pintype "input"))
      (node (ref "C3") (pin "2") (pinfunction "2_2") (pintype "input"))
      (node (ref "C32") (pin "1") (pinfunction "1_1") (pintype "unspecified"))
      (node (ref "C33") (pin "1") (pinfunction "1_1") (pintype "unspecified"))
      (node (ref "C4") (pin "2") (pinfunction "2_2") (pintype "input"))
      (node (ref "C5") (pin "2") (pinfunction "2_2") (pintype "unspecified"))
      (node (ref "C6") (pin "2") (pinfunction "2_2") (pintype "unspecified"))
      (node (ref "C7") (pin "2") (pinfunction "2_2") (pintype "unspecified"))
      (node (ref "C8") (pin "2") (pinfunction "2_2") (pintype "input"))
      (node (ref "C9") (pin "2") (pinfunction "2_2") (pintype "unspecified"))
      (node (ref "D1") (pin "1") (pinfunction "1_1") (pintype "unspecified"))
      (node (ref "D2") (pin "1") (pinfunction "1_1") (pintype "unspecified"))
      (node (ref "D6") (pin "2") (pinfunction "2_2") (pintype "unspecified"))
      (node (ref "D7") (pin "2") (pinfunction "2_2") (pintype "unspecified"))
      (node (ref "ESPC6") (pin "1") (pinfunction "GND_1") (pintype "unspecified"))
      (node (ref "ESPC6") (pin "28") (pinfunction "GND_28") (pintype "unspecified"))
      (node (ref "ESPC6") (pin "29") (pinfunction "GND_29") (pintype "unspecified"))
      (node (ref "ESPC6") (pin "30") (pinfunction "GND_30") (pintype "unspecified"))
      (node (ref "ESPC6") (pin "31") (pinfunction "GND_31") (pintype "unspecified"))
      (node (ref "ESPC6") (pin "32") (pinfunction "GND_32") (pintype "unspecified"))
      (node (ref "ESPC6") (pin "33") (pinfunction "GND_33") (pintype "unspecified"))
      (node (ref "ESPC6") (pin "34") (pinfunction "GND_34") (pintype "unspecified"))
      (node (ref "ESPC6") (pin "35") (pinfunction "GND_35") (pintype "unspecified"))
      (node (ref "ESPC6") (pin "36") (pinfunction "GND_36") (pintype "unspecified"))
      (node (ref "ESPC6") (pin "37") (pinfunction "GND_37") (pintype "unspecified"))
      (node (ref "GND1") (pin "1") (pinfunction "1_1") (pintype "unspecified"))
      (node (ref "GND1") (pin "2") (pinfunction "2_2") (pintype "unspecified"))
      (node (ref "GND2") (pin "1") (pinfunction "1_1") (pintype "unspecified"))
      (node (ref "GND2") (pin "2") (pinfunction "2_2") (pintype "unspecified"))
      (node (ref "I1C") (pin "1") (pinfunction "1_1") (pintype "unspecified"))
      (node (ref "IOS") (pin "10") (pinfunction "10_10") (pintype "unspecified"))
      (node (ref "IOS") (pin "11") (pinfunction "11_11") (pintype "unspecified"))
      (node (ref "IOS") (pin "12") (pinfunction "12_12") (pintype "unspecified"))
      (node (ref "IOS") (pin "13") (pinfunction "13_13") (pintype "unspecified"))
      (node (ref "IOS") (pin "14") (pinfunction "14_14") (pintype "unspecified"))
      (node (ref "IOS") (pin "15") (pinfunction "15_15") (pintype "unspecified"))
      (node (ref "IOS") (pin "16") (pinfunction "16_16") (pintype "unspecified"))
      (node (ref "IOS") (pin "9") (pinfunction "9_9") (pintype "unspecified"))
      (node (ref "IOX") (pin "5") (pinfunction "A2_5") (pintype "unspecified"))
      (node (ref "IOX") (pin "8") (pinfunction "VSS_8") (pintype "passive"))
      (node (ref "J1V0") (pin "2") (pinfunction "2_2") (pintype "unspecified"))
      (node (ref "J6") (pin "2") (pinfunction "2_2") (pintype "unspecified"))
      (node (ref "JPWR") (pin "2") (pinfunction "2_2") (pintype "unspecified"))
      (node (ref "L1V3") (pin "1") (pinfunction "K_1") (pintype "unspecified"))
      (node (ref "MCL") (pin "3") (pinfunction "VSS_3") (pintype "unspecified"))
      (node (ref "OLED") (pin "1") (pinfunction "GND_1") (pintype "unspecified"))
      (node (ref "R1") (pin "2") (pinfunction "2_2") (pintype "unspecified"))
      (node (ref "R13") (pin "2") (pinfunction "2_2") (pintype "input"))
      (node (ref "R19") (pin "2") (pinfunction "2_2") (pintype "unspecified"))
      (node (ref "R2") (pin "2") (pinfunction "2_2") (pintype "input"))
      (node (ref "R21") (pin "2") (pinfunction "2_2") (pintype "unspecified"))
      (node (ref "RC1") (pin "1") (pinfunction "1_1") (pintype "unspecified"))
      (node (ref "RC2") (pin "1") (pinfunction "1_1") (pintype "input"))
      (node (ref "RLED1") (pin "2") (pinfunction "C_2") (pintype "input"))
      (node (ref "RLED2") (pin "2") (pinfunction "C_2") (pintype "input"))
      (node (ref "RR4") (pin "1") (pinfunction "1_1") (pintype "input"))
      (node (ref "RST") (pin "3") (pinfunction "3_3") (pintype "unspecified"))
      (node (ref "RST") (pin "4") (pinfunction "4_4") (pintype "unspecified"))
      (node (ref "RU1") (pin "5") (pinfunction "GND_5") (pintype "unspecified"))
      (node (ref "RU2") (pin "7") (pinfunction "GND_7") (pintype "unspecified"))
      (node (ref "S1") (pin "3") (pinfunction "3_3") (pintype "unspecified"))
      (node (ref "S1") (pin "4") (pinfunction "4_4") (pintype "unspecified"))
      (node (ref "SI1") (pin "3") (pinfunction "3_3") (pintype "unspecified"))
      (node (ref "SI1") (pin "4") (pinfunction "4_4") (pintype "unspecified"))
      (node (ref "SSTP") (pin "3") (pinfunction "3_3") (pintype "unspecified"))
      (node (ref "SSTP") (pin "4") (pinfunction "4_4") (pintype "unspecified"))
      (node (ref "SSTR") (pin "3") (pinfunction "3_3") (pintype "unspecified"))
      (node (ref "SSTR") (pin "4") (pinfunction "4_4") (pintype "unspecified"))
      (node (ref "U1") (pin "1") (pinfunction "1_1") (pintype "unspecified"))
      (node (ref "U1V0") (pin "2") (pinfunction "GND_2") (pintype "unspecified"))
      (node (ref "U1V3") (pin "1") (pinfunction "ADJ/GND_1") (pintype "unspecified"))
      (node (ref "U2") (pin "2") (pinfunction "GND_2") (pintype "unspecified"))
      (node (ref "U4") (pin "11") (pinfunction "GND_11") (pintype "unspecified"))
      (node (ref "U4") (pin "6") (pinfunction "GND_6") (pintype "unspecified"))
      (node (ref "USB") (pin "1") (pinfunction "SHELL_1") (pintype "unspecified"))
      (node (ref "USB") (pin "2") (pinfunction "SHELL_2") (pintype "unspecified"))
      (node (ref "USB") (pin "3") (pinfunction "SHELL_3") (pintype "unspecified"))
      (node (ref "USB") (pin "4") (pinfunction "SHELL_4") (pintype "unspecified"))
      (node (ref "USB") (pin "A1B12") (pinfunction "GND_A1B12") (pintype "unspecified"))
      (node (ref "USB") (pin "B1A12") (pinfunction "GND_B1A12") (pintype "unspecified"))
      (node (ref "UT") (pin "2") (pinfunction "GND_2") (pintype "unspecified"))
      (node (ref "UT") (pin "4") (pinfunction "ADD0_4") (pintype "unspecified"))
      (node (ref "VVC5") (pin "2") (pinfunction "2_2") (pintype "unspecified"))
      (node (ref "XC1") (pin "2") (pinfunction "2_2") (pintype "unspecified"))
      (node (ref "XC2") (pin "2") (pinfunction "2_2") (pintype "input"))
      (node (ref "XC3") (pin "1") (pinfunction "1_1") (pintype "unspecified"))
      (node (ref "XC4") (pin "2") (pinfunction "2_2") (pintype "input"))
      (node (ref "XP2") (pin "1") (pinfunction "1_1") (pintype "input"))
      (node (ref "XP4") (pin "1") (pinfunction "1_1") (pintype "input"))
      (node (ref "XR1") (pin "1") (pinfunction "1_1") (pintype "unspecified"))
      (node (ref "XU1") (pin "1") (pinfunction "GND_1") (pintype "unspecified"))
    )
    (net (code "13") (name "IO2") (class "Default")
      (node (ref "ESPC6") (pin "27") (pinfunction "IO2_27") (pintype "unspecified"))
      (node (ref "J7") (pin "2") (pinfunction "2_2") (pintype "unspecified"))
    )
    (net (code "14") (name "IO8") (class "Default")
      (node (ref "D4") (pin "1") (pinfunction "K_1") (pintype "unspecified"))
      (node (ref "ESPC6") (pin "10") (pinfunction "IO8_10") (pintype "unspecified"))
      (node (ref "J8") (pin "1") (pinfunction "1_1") (pintype "input"))
    )
    (net (code "15") (name "IO9") (class "Default")
      (node (ref "BOOT") (pin "1") (pinfunction "1_1") (pintype "unspecified"))
      (node (ref "BOOT") (pin "2") (pinfunction "2_2") (pintype "unspecified"))
      (node (ref "C2") (pin "2") (pinfunction "2_2") (pintype "input"))
      (node (ref "ESPC6") (pin "15") (pinfunction "IO9_15") (pintype "unspecified"))
      (node (ref "J9") (pin "1") (pinfunction "1_1") (pintype "input"))
    )
    (net (code "16") (name "IO15") (class "Default")
      (node (ref "ESPC6") (pin "23") (pinfunction "IO15_23") (pintype "unspecified"))
      (node (ref "J10") (pin "1") (pinfunction "1_1") (pintype "input"))
      (node (ref "J3") (pin "1") (pinfunction "1_1") (pintype "unspecified"))
    )
    (net (code "17") (name "IO22") (class "Default")
      (node (ref "ESPC6") (pin "20") (pinfunction "IO22_20") (pintype "unspecified"))
      (node (ref "J2") (pin "2") (pinfunction "2_2") (pintype "unspecified"))
      (node (ref "RIO22") (pin "1") (pinfunction "1_1") (pintype "input"))
      (node (ref "RR9") (pin "1") (pinfunction "1_1") (pintype "input"))
      (node (ref "RU2") (pin "1") (pinfunction "1A_1") (pintype "unspecified"))
      (node (ref "SI1") (pin "2") (pinfunction "2_2") (pintype "unspecified"))
    )
    (net (code "18") (name "IO23") (class "Default")
      (node (ref "ESPC6") (pin "21") (pinfunction "IO23_21") (pintype "unspecified"))
      (node (ref "J2") (pin "1") (pinfunction "1_1") (pintype "unspecified"))
      (node (ref "RIO23") (pin "1") (pinfunction "1_1") (pintype "input"))
      (node (ref "RU2") (pin "4") (pinfunction "2Y_4") (pintype "unspecified"))
      (node (ref "RU2") (pin "5") (pinfunction "3A_5") (pintype "unspecified"))
      (node (ref "S1") (pin "2") (pinfunction "2_2") (pintype "unspecified"))
    )
    (net (code "19") (name "LED_RXD") (class "Default")
      (node (ref "RLRX") (pin "1") (pinfunction "1_1") (pintype "input"))
      (node (ref "RR8") (pin "1") (pinfunction "1_1") (pintype "input"))
      (node (ref "RU2") (pin "6") (pinfunction "3Y_6") (pintype "unspecified"))
    )
    (net (code "20") (name "LED_TXD") (class "Default")
      (node (ref "RLTX") (pin "1") (pinfunction "1_1") (pintype "input"))
      (node (ref "RR7") (pin "2") (pinfunction "2_2") (pintype "input"))
      (node (ref "RU2") (pin "11") (pinfunction "5A_11") (pintype "unspecified"))
      (node (ref "RU2") (pin "2") (pinfunction "1Y_2") (pintype "unspecified"))
    )
    (net (code "21") (name "Net-(3V3CL-A)") (class "Default")
      (node (ref "3V3CL") (pin "2") (pinfunction "A_2") (pintype "unspecified"))
      (node (ref "R3") (pin "2") (pinfunction "2_2") (pintype "input"))
    )
    (net (code "22") (name "Net-(5V0CL-A)") (class "Default")
      (node (ref "5V0CL") (pin "2") (pinfunction "A_2") (pintype "unspecified"))
      (node (ref "R6") (pin "2") (pinfunction "2_2") (pintype "input"))
    )
    (net (code "23") (name "Net-(D3-A)") (class "Default")
      (node (ref "D3") (pin "1") (pinfunction "A_1") (pintype "unspecified"))
      (node (ref "USB") (pin "A4B9") (pinfunction "VBUS_A4B9") (pintype "unspecified"))
      (node (ref "USB") (pin "B4A9") (pinfunction "VBUS_B4A9") (pintype "unspecified"))
    )
    (net (code "24") (name "Net-(D4-A)") (class "Default")
      (node (ref "D4") (pin "2") (pinfunction "A_2") (pintype "unspecified"))
      (node (ref "R15") (pin "2") (pinfunction "2_2") (pintype "input"))
      (node (ref "R16") (pin "1") (pinfunction "1_1") (pintype "input"))
    )
    (net (code "25") (name "Net-(IOX-RESET#)") (class "Default")
      (node (ref "IOX") (pin "15") (pinfunction "RESET#_15") (pintype "unspecified"))
      (node (ref "R25") (pin "1") (pinfunction "1_1") (pintype "input"))
    )
    (net (code "26") (name "Net-(L1V3-A)") (class "Default")
      (node (ref "L1V3") (pin "2") (pinfunction "A_2") (pintype "unspecified"))
      (node (ref "R22") (pin "2") (pinfunction "2_2") (pintype "input"))
    )
    (net (code "27") (name "Net-(MCL-DIN)") (class "Default")
      (node (ref "MCL") (pin "4") (pinfunction "DIN_4") (pintype "unspecified"))
      (node (ref "R16") (pin "2") (pinfunction "2_2") (pintype "input"))
    )
    (net (code "28") (name "Net-(R4-Pad2)") (class "Default")
      (node (ref "R4") (pin "2") (pinfunction "2_2") (pintype "input"))
      (node (ref "SSTP") (pin "1") (pinfunction "1_1") (pintype "unspecified"))
    )
    (net (code "29") (name "Net-(R7-Pad2)") (class "Default")
      (node (ref "R7") (pin "2") (pinfunction "2_2") (pintype "input"))
      (node (ref "SSTR") (pin "1") (pinfunction "1_1") (pintype "unspecified"))
    )
    (net (code "30") (name "Net-(R11-Pad2)") (class "Default")
      (node (ref "R11") (pin "2") (pinfunction "2_2") (pintype "input"))
      (node (ref "SI1") (pin "1") (pinfunction "1_1") (pintype "unspecified"))
    )
    (net (code "31") (name "Net-(R14-Pad2)") (class "Default")
      (node (ref "R14") (pin "2") (pinfunction "2_2") (pintype "input"))
      (node (ref "S1") (pin "1") (pinfunction "1_1") (pintype "unspecified"))
    )
    (net (code "32") (name "Net-(RD1-A)") (class "Default")
      (node (ref "RC2") (pin "2") (pinfunction "2_2") (pintype "input"))
      (node (ref "RD1") (pin "2") (pinfunction "A_2") (pintype "unspecified"))
      (node (ref "RR6") (pin "1") (pinfunction "1_1") (pintype "input"))
      (node (ref "RU2") (pin "13") (pinfunction "6A_13") (pintype "unspecified"))
    )
    (net (code "33") (name "Net-(RD1-K)") (class "Default")
      (node (ref "RD1") (pin "1") (pinfunction "K_1") (pintype "unspecified"))
      (node (ref "RR6") (pin "2") (pinfunction "2_2") (pintype "input"))
      (node (ref "RU1") (pin "4") (pinfunction "DI_4") (pintype "unspecified"))
      (node (ref "RU2") (pin "10") (pinfunction "5Y_10") (pintype "unspecified"))
    )
    (net (code "34") (name "Net-(RLED1-A)") (class "Default")
      (node (ref "RLED1") (pin "1") (pinfunction "A_1") (pintype "input"))
      (node (ref "RR7") (pin "1") (pinfunction "1_1") (pintype "input"))
    )
    (net (code "35") (name "Net-(RLED2-A)") (class "Default")
      (node (ref "RLED2") (pin "1") (pinfunction "A_1") (pintype "input"))
      (node (ref "RR8") (pin "2") (pinfunction "2_2") (pintype "input"))
    )
    (net (code "36") (name "Net-(RR1-Pad2)") (class "Default")
      (node (ref "RR1") (pin "2") (pinfunction "2_2") (pintype "input"))
      (node (ref "RR2") (pin "1") (pinfunction "1_1") (pintype "input"))
    )
    (net (code "37") (name "Net-(RU1-DE)") (class "Default")
      (node (ref "RU1") (pin "2") (pinfunction "RE#_2") (pintype "unspecified"))
      (node (ref "RU1") (pin "3") (pinfunction "DE_3") (pintype "unspecified"))
      (node (ref "RU2") (pin "12") (pinfunction "6Y_12") (pintype "unspecified"))
    )
    (net (code "38") (name "Net-(RU1-RO)") (class "Default")
      (node (ref "RR5") (pin "1") (pinfunction "1_1") (pintype "input"))
      (node (ref "RU1") (pin "1") (pinfunction "RO_1") (pintype "unspecified"))
      (node (ref "RU2") (pin "9") (pinfunction "4A_9") (pintype "unspecified"))
    )
    (net (code "39") (name "Net-(RU2-2A)") (class "Default")
      (node (ref "RU2") (pin "3") (pinfunction "2A_3") (pintype "unspecified"))
      (node (ref "RU2") (pin "8") (pinfunction "4Y_8") (pintype "unspecified"))
    )
    (net (code "40") (name "Net-(USB-CC1)") (class "Default")
      (node (ref "R2") (pin "1") (pinfunction "1_1") (pintype "input"))
      (node (ref "USB") (pin "A5") (pinfunction "CC1_A5") (pintype "unspecified"))
    )
    (net (code "41") (name "Net-(USB-CC2)") (class "Default")
      (node (ref "R1") (pin "1") (pinfunction "1_1") (pintype "unspecified"))
      (node (ref "USB") (pin "B5") (pinfunction "CC2_B5") (pintype "unspecified"))
    )
    (net (code "42") (name "Net-(USB-DN1)") (class "Default")
      (node (ref "D2") (pin "2") (pinfunction "2_2") (pintype "unspecified"))
      (node (ref "R9") (pin "1") (pinfunction "1_1") (pintype "input"))
      (node (ref "USB") (pin "A7") (pinfunction "DN1_A7") (pintype "unspecified"))
      (node (ref "USB") (pin "B7") (pinfunction "DN2_B7") (pintype "unspecified"))
    )
    (net (code "43") (name "Net-(USB-DP1)") (class "Default")
      (node (ref "D1") (pin "2") (pinfunction "2_2") (pintype "unspecified"))
      (node (ref "R8") (pin "1") (pinfunction "1_1") (pintype "input"))
      (node (ref "USB") (pin "A6") (pinfunction "DP1_A6") (pintype "unspecified"))
      (node (ref "USB") (pin "B6") (pinfunction "DP2_B6") (pintype "unspecified"))
    )
    (net (code "44") (name "Net-(XD1-A-Pad1)") (class "Default")
      (node (ref "XD1") (pin "1") (pinfunction "A_1") (pintype "unspecified"))
      (node (ref "XD1") (pin "3") (pinfunction "A_3") (pintype "unspecified"))
      (node (ref "XL1") (pin "1") (pinfunction "1_1") (pintype "unspecified"))
      (node (ref "XU1") (pin "3") (pinfunction "SW_3") (pintype "unspecified"))
      (node (ref "XU1") (pin "6") (pinfunction "SW_6") (pintype "unspecified"))
    )
    (net (code "45") (name "Net-(XP5-Pad1)") (class "Default")
      (node (ref "XP5") (pin "1") (pinfunction "1_1") (pintype "input"))
      (node (ref "XR5") (pin "1") (pinfunction "1_1") (pintype "unspecified"))
    )
    (net (code "46") (name "Net-(XU1-EN)") (class "Default")
      (node (ref "XR3") (pin "2") (pinfunction "2_2") (pintype "unspecified"))
      (node (ref "XU1") (pin "2") (pinfunction "EN_2") (pintype "unspecified"))
    )
    (net (code "47") (name "OL_SCL") (class "Default")
      (node (ref "ESPC6") (pin "7") (pinfunction "IO7_7") (pintype "unspecified"))
      (node (ref "I1C") (pin "3") (pinfunction "3_3") (pintype "unspecified"))
      (node (ref "IOX") (pin "1") (pinfunction "SCL_1") (pintype "unspecified"))
      (node (ref "OLED") (pin "3") (pinfunction "SCL_3") (pintype "unspecified"))
      (node (ref "R33") (pin "2") (pinfunction "2_2") (pintype "input"))
      (node (ref "UT") (pin "1") (pinfunction "SCL_1") (pintype "unspecified"))
    )
    (net (code "48") (name "OL_SDA") (class "Default")
      (node (ref "ESPC6") (pin "6") (pinfunction "IO6_6") (pintype "unspecified"))
      (node (ref "I1C") (pin "4") (pinfunction "4_4") (pintype "unspecified"))
      (node (ref "IOX") (pin "2") (pinfunction "SDA_2") (pintype "bidirectional"))
      (node (ref "OLED") (pin "4") (pinfunction "SDA_4") (pintype "unspecified"))
      (node (ref "R30") (pin "2") (pinfunction "2_2") (pintype "input"))
      (node (ref "UT") (pin "6") (pinfunction "SDA_6") (pintype "unspecified"))
    )
    (net (code "49") (name "SLA+") (class "Default")
      (node (ref "SLA") (pin "1") (pinfunction "1_1") (pintype "unspecified"))
      (node (ref "SLA") (pin "2") (pinfunction "2_2") (pintype "unspecified"))
      (node (ref "U4") (pin "10") (pinfunction "OUT1_10") (pintype "unspecified"))
    )
    (net (code "50") (name "SLA-") (class "Default")
      (node (ref "NO") (pin "1") (pinfunction "1_1") (pintype "unspecified"))
      (node (ref "NO") (pin "2") (pinfunction "2_2") (pintype "unspecified"))
      (node (ref "U4") (pin "9") (pinfunction "OUT2_9") (pintype "unspecified"))
    )
    (net (code "51") (name "SLAN") (class "Default")
      (node (ref "ESPC6") (pin "11") (pinfunction "IO10_11") (pintype "unspecified"))
      (node (ref "U4") (pin "3") (pinfunction "IN2_3") (pintype "unspecified"))
    )
    (net (code "52") (name "SLAP") (class "Default")
      (node (ref "ESPC6") (pin "12") (pinfunction "IO11_12") (pintype "unspecified"))
      (node (ref "U4") (pin "2") (pinfunction "IN1_2") (pintype "unspecified"))
    )
    (net (code "53") (name "SLB+") (class "Default")
      (node (ref "SLB") (pin "1") (pinfunction "1_1") (pintype "unspecified"))
      (node (ref "SLB") (pin "2") (pinfunction "2_2") (pintype "unspecified"))
      (node (ref "U4") (pin "8") (pinfunction "OUT3_8") (pintype "unspecified"))
    )
    (net (code "54") (name "SLB-") (class "Default")
      (node (ref "SLA1") (pin "1") (pinfunction "1_1") (pintype "unspecified"))
      (node (ref "SLA1") (pin "2") (pinfunction "2_2") (pintype "unspecified"))
      (node (ref "U4") (pin "7") (pinfunction "OUT4_7") (pintype "unspecified"))
    )
    (net (code "55") (name "SLBN") (class "Default")
      (node (ref "ESPC6") (pin "4") (pinfunction "IO4_4") (pintype "unspecified"))
      (node (ref "U4") (pin "5") (pinfunction "IN4_5") (pintype "unspecified"))
    )
    (net (code "56") (name "SLBP") (class "Default")
      (node (ref "ESPC6") (pin "5") (pinfunction "IO5_5") (pintype "unspecified"))
      (node (ref "U4") (pin "4") (pinfunction "IN3_4") (pintype "unspecified"))
    )
    (net (code "57") (name "STP") (class "Default")
      (node (ref "ESPC6") (pin "19") (pinfunction "IO21_19") (pintype "unspecified"))
      (node (ref "SSTP") (pin "2") (pinfunction "2_2") (pintype "unspecified"))
    )
    (net (code "58") (name "STR") (class "Default")
      (node (ref "ESPC6") (pin "18") (pinfunction "IO20_18") (pintype "unspecified"))
      (node (ref "SSTR") (pin "2") (pinfunction "2_2") (pintype "unspecified"))
    )
    (net (code "59") (name "SW1") (class "Default")
      (node (ref "IOS") (pin "1") (pinfunction "1_1") (pintype "unspecified"))
      (node (ref "IOX") (pin "6") (pinfunction "IO0_6") (pintype "bidirectional"))
      (node (ref "S2") (pin "1") (pinfunction "1_1") (pintype "input"))
    )
    (net (code "60") (name "SW2") (class "Default")
      (node (ref "IOS") (pin "2") (pinfunction "2_2") (pintype "unspecified"))
      (node (ref "IOX") (pin "7") (pinfunction "IO1_7") (pintype "bidirectional"))
      (node (ref "S3") (pin "1") (pinfunction "1_1") (pintype "input"))
    )
    (net (code "61") (name "SW3") (class "Default")
      (node (ref "IOS") (pin "3") (pinfunction "3_3") (pintype "unspecified"))
      (node (ref "IOX") (pin "9") (pinfunction "IO2_9") (pintype "bidirectional"))
      (node (ref "S4") (pin "1") (pinfunction "1_1") (pintype "input"))
    )
    (net (code "62") (name "SW4") (class "Default")
      (node (ref "IOS") (pin "4") (pinfunction "4_4") (pintype "unspecified"))
      (node (ref "IOX") (pin "10") (pinfunction "IO3_10") (pintype "bidirectional"))
      (node (ref "S5") (pin "1") (pinfunction "1_1") (pintype "input"))
    )
    (net (code "63") (name "SW5") (class "Default")
      (node (ref "IOS") (pin "5") (pinfunction "5_5") (pintype "unspecified"))
      (node (ref "IOX") (pin "11") (pinfunction "IO4_11") (pintype "bidirectional"))
      (node (ref "S6") (pin "1") (pinfunction "1_1") (pintype "input"))
    )
    (net (code "64") (name "SW6") (class "Default")
      (node (ref "IOS") (pin "6") (pinfunction "6_6") (pintype "unspecified"))
      (node (ref "IOX") (pin "12") (pinfunction "IO5_12") (pintype "bidirectional"))
      (node (ref "S7") (pin "1") (pinfunction "1_1") (pintype "input"))
    )
    (net (code "65") (name "SW7") (class "Default")
      (node (ref "IOS") (pin "7") (pinfunction "7_7") (pintype "unspecified"))
      (node (ref "IOX") (pin "13") (pinfunction "IO6_13") (pintype "bidirectional"))
      (node (ref "S8") (pin "1") (pinfunction "1_1") (pintype "input"))
    )
    (net (code "66") (name "SW8") (class "Default")
      (node (ref "IOS") (pin "8") (pinfunction "8_8") (pintype "unspecified"))
      (node (ref "IOX") (pin "14") (pinfunction "IO7_14") (pintype "bidirectional"))
      (node (ref "S9") (pin "1") (pinfunction "1_1") (pintype "input"))
    )
    (net (code "67") (name "UART_RXD") (class "Default")
      (node (ref "ESPC6") (pin "24") (pinfunction "RXD0_24") (pintype "unspecified"))
      (node (ref "J3") (pin "2") (pinfunction "2_2") (pintype "unspecified"))
    )
    (net (code "68") (name "UART_TXD") (class "Default")
      (node (ref "ESPC6") (pin "25") (pinfunction "TXD0_25") (pintype "unspecified"))
      (node (ref "J7") (pin "1") (pinfunction "1_1") (pintype "unspecified"))
    )
    (net (code "69") (name "USB_DN") (class "Default")
      (node (ref "ESPC6") (pin "13") (pinfunction "IO12_13") (pintype "unspecified"))
      (node (ref "R9") (pin "2") (pinfunction "2_2") (pintype "input"))
    )
    (net (code "70") (name "USB_DP") (class "Default")
      (node (ref "ESPC6") (pin "14") (pinfunction "IO13_14") (pintype "unspecified"))
      (node (ref "R10") (pin "2") (pinfunction "2_2") (pintype "input"))
      (node (ref "R8") (pin "2") (pinfunction "2_2") (pintype "input"))
    )
    (net (code "71") (name "VB") (class "Default")
      (node (ref "ESPC6") (pin "26") (pinfunction "IO3_26") (pintype "unspecified"))
      (node (ref "R12") (pin "2") (pinfunction "2_2") (pintype "input"))
      (node (ref "R13") (pin "1") (pinfunction "1_1") (pintype "input"))
    )
    (net (code "72") (name "VCC_3.3V") (class "Default")
      (node (ref "C16") (pin "1") (pinfunction "1_1") (pintype "input"))
      (node (ref "C18") (pin "1") (pinfunction "1_1") (pintype "unspecified"))
      (node (ref "C4") (pin "1") (pinfunction "1_1") (pintype "input"))
      (node (ref "C5") (pin "1") (pinfunction "1_1") (pintype "unspecified"))
      (node (ref "ESPC6") (pin "2") (pinfunction "3V3_2") (pintype "unspecified"))
      (node (ref "J6") (pin "1") (pinfunction "1_1") (pintype "unspecified"))
      (node (ref "R22") (pin "1") (pinfunction "1_1") (pintype "input"))
      (node (ref "R5") (pin "1") (pinfunction "1_1") (pintype "input"))
      (node (ref "RC1") (pin "2") (pinfunction "2_2") (pintype "unspecified"))
      (node (ref "RR3") (pin "2") (pinfunction "2_2") (pintype "input"))
      (node (ref "RR5") (pin "2") (pinfunction "2_2") (pintype "input"))
      (node (ref "RR9") (pin "2") (pinfunction "2_2") (pintype "input"))
      (node (ref "RU1") (pin "8") (pinfunction "VCC_8") (pintype "unspecified"))
      (node (ref "RU2") (pin "14") (pinfunction "VCC_14") (pintype "unspecified"))
      (node (ref "U1V3") (pin "2") (pinfunction "VOUT_2") (pintype "unspecified"))
      (node (ref "U1V3") (pin "4") (pinfunction "VOUT_4") (pintype "unspecified"))
    )
    (net (code "73") (name "VCC_5V") (class "Default")
      (node (ref "C10") (pin "1") (pinfunction "1_1") (pintype "unspecified"))
      (node (ref "C12") (pin "1") (pinfunction "1_1") (pintype "input"))
      (node (ref "C20") (pin "2") (pinfunction "2_2") (pintype "input"))
      (node (ref "C6") (pin "1") (pinfunction "1_1") (pintype "unspecified"))
      (node (ref "C7") (pin "1") (pinfunction "1_1") (pintype "unspecified"))
      (node (ref "C8") (pin "1") (pinfunction "1_1") (pintype "input"))
      (node (ref "C9") (pin "1") (pinfunction "1_1") (pintype "unspecified"))
      (node (ref "D3") (pin "2") (pinfunction "K_2") (pintype "unspecified"))
      (node (ref "D5") (pin "2") (pinfunction "K_2") (pintype "unspecified"))
      (node (ref "R10") (pin "1") (pinfunction "1_1") (pintype "input"))
      (node (ref "U1V0") (pin "5") (pinfunction "IN_5") (pintype "unspecified"))
      (node (ref "U1V3") (pin "3") (pinfunction "VIN_3") (pintype "unspecified"))
      (node (ref "U2") (pin "1") (pinfunction "IN_1") (pintype "unspecified"))
      (node (ref "VVC5") (pin "1") (pinfunction "1_1") (pintype "unspecified"))
      (node (ref "XC1") (pin "1") (pinfunction "1_1") (pintype "unspecified"))
      (node (ref "XC2") (pin "1") (pinfunction "1_1") (pintype "input"))
      (node (ref "XL1") (pin "2") (pinfunction "2_2") (pintype "unspecified"))
      (node (ref "XP1") (pin "1") (pinfunction "1_1") (pintype "input"))
      (node (ref "XR3") (pin "1") (pinfunction "1_1") (pintype "unspecified"))
      (node (ref "XU1") (pin "4") (pinfunction "VIN_4") (pintype "unspecified"))
    )
    (net (code "74") (name "VDCIN+5V") (class "Default")
      (node (ref "D5") (pin "1") (pinfunction "A_1") (pintype "unspecified"))
      (node (ref "JPWR") (pin "1") (pinfunction "1_1") (pintype "unspecified"))
      (node (ref "U1") (pin "2") (pinfunction "2_2") (pintype "unspecified"))
    )
    (net (code "75") (name "VI-1") (class "Default")
      (node (ref "JVI1") (pin "1") (pinfunction "1_1") (pintype "unspecified"))
      (node (ref "JVI1") (pin "2") (pinfunction "2_2") (pintype "unspecified"))
      (node (ref "R18") (pin "1") (pinfunction "1_1") (pintype "unspecified"))
    )
    (net (code "76") (name "VI-2") (class "Default")
      (node (ref "JVI2") (pin "1") (pinfunction "1_1") (pintype "unspecified"))
      (node (ref "JVI2") (pin "2") (pinfunction "2_2") (pintype "unspecified"))
      (node (ref "R20") (pin "1") (pinfunction "1_1") (pintype "unspecified"))
    )
    (net (code "77") (name "unconnected-(ESPC6-NC-Pad22)") (class "Default")
      (node (ref "ESPC6") (pin "22") (pinfunction "NC_22") (pintype "unspecified+no_connect"))
    )
    (net (code "78") (name "unconnected-(MCL-DOUT-Pad2)") (class "Default")
      (node (ref "MCL") (pin "2") (pinfunction "DOUT_2") (pintype "unspecified+no_connect"))
    )
    (net (code "79") (name "unconnected-(U1V0-FLT#-Pad3)") (class "Default")
      (node (ref "U1V0") (pin "3") (pinfunction "FLT#_3") (pintype "unspecified"))
    )
    (net (code "80") (name "unconnected-(U2-NC-Pad4)") (class "Default")
      (node (ref "U2") (pin "4") (pinfunction "NC_4") (pintype "unspecified"))
    )
    (net (code "81") (name "unconnected-(USB-SBU1-PadA8)") (class "Default")
      (node (ref "USB") (pin "A8") (pinfunction "SBU1_A8") (pintype "unspecified+no_connect"))
    )
    (net (code "82") (name "unconnected-(USB-SBU2-PadB8)") (class "Default")
      (node (ref "USB") (pin "B8") (pinfunction "SBU2_B8") (pintype "unspecified+no_connect"))
    )
    (net (code "83") (name "unconnected-(UT-ALERT-Pad3)") (class "Default")
      (node (ref "UT") (pin "3") (pinfunction "ALERT_3") (pintype "unspecified"))
    )
  )
)
